# GSM_UnUsed.net
KiCad netlist of a schematic drawn in Altium Designer
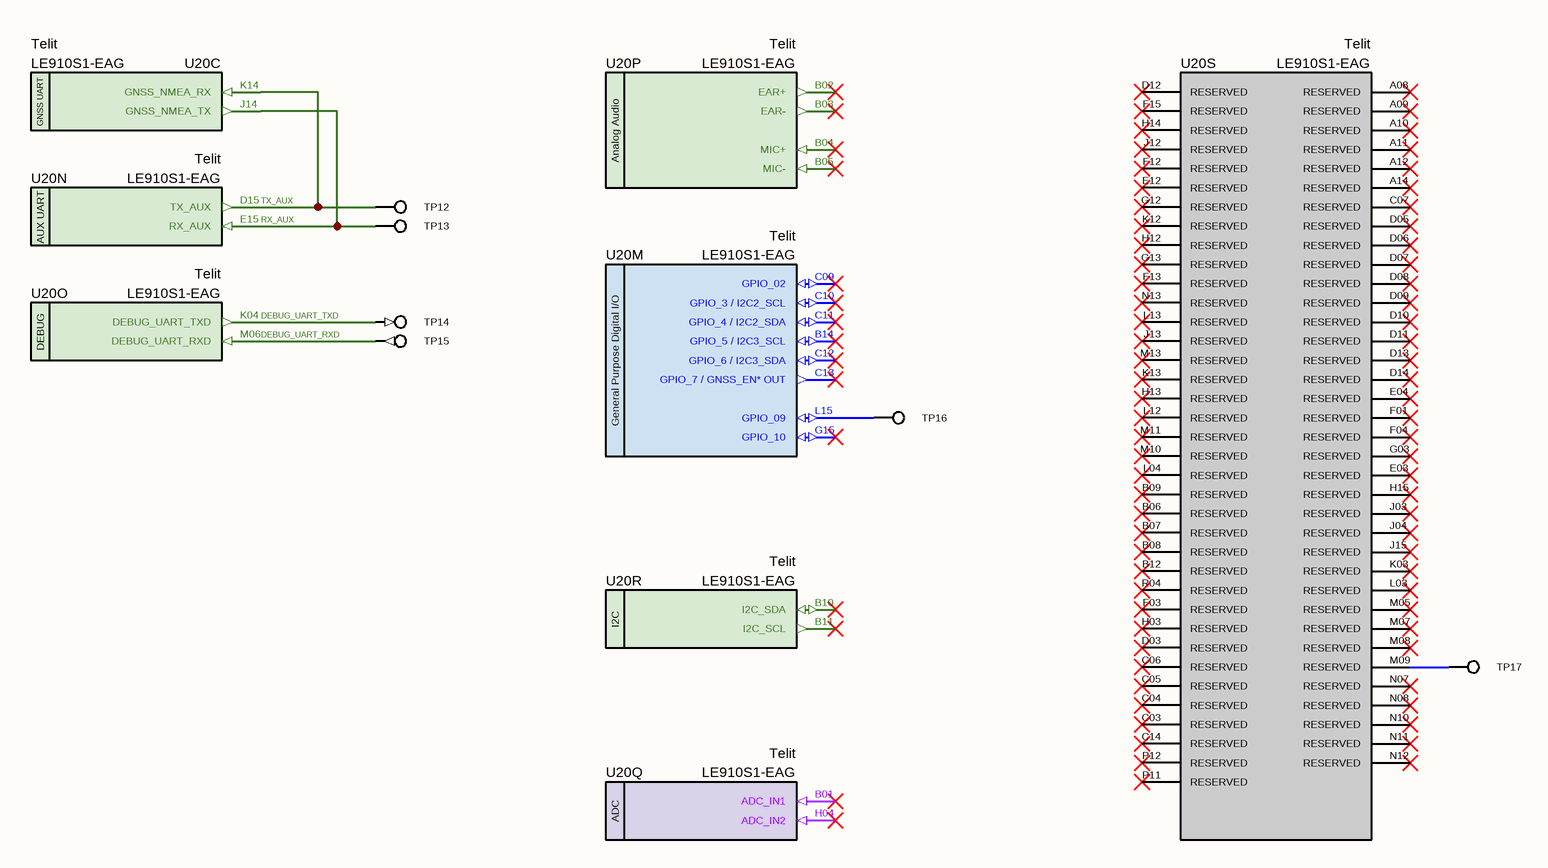
[diagram p0: GSM UnUsed.SchDoc]

(export (version "E")
  (design (tool "Eeschema 10.0.6"))
  (components
    (comp (ref "TP12")
      (value "TP - GSM_Power_EN")
      (footprint "TP")
      (description "Test Point")
      (libsource (lib "Akkoyun") (part "PCB - Test Point"))
    )
    (comp (ref "TP13")
      (value "TP - GSM_Power_EN")
      (footprint "TP")
      (description "Test Point")
      (libsource (lib "Akkoyun") (part "PCB - Test Point"))
    )
    (comp (ref "TP14")
      (value "TP - GSM_Power_EN")
      (footprint "TP")
      (description "Test Point")
      (libsource (lib "Akkoyun") (part "PCB - Test Point"))
    )
    (comp (ref "TP15")
      (value "TP - GSM_Power_EN")
      (footprint "TP")
      (description "Test Point")
      (libsource (lib "Akkoyun") (part "PCB - Test Point"))
    )
    (comp (ref "TP16")
      (value "TP - GSM_Power_EN")
      (footprint "TP")
      (description "Test Point")
      (libsource (lib "Akkoyun") (part "PCB - Test Point"))
    )
    (comp (ref "TP17")
      (value "TP - GSM_Power_EN")
      (footprint "TP")
      (description "Test Point")
      (libsource (lib "Akkoyun") (part "PCB - Test Point"))
    )
    (comp (ref "U20")
      (value "LE910S1-EAG LTE GSM Module")
      (footprint "LE910 GSM Modem")
      (description "Telit LE910S1-EAG GPRS/GNSS Module")
      (fields
        (field (name "MANUFACTURER PART NUMBER") "LE910S1-EAG")
        (field (name "MANUFACTURER NAME") "Telit")
      )
      (libsource (lib "") (part "IC - LE910S1-EAG_1"))
    )
  )
  (nets
    (net (code "1") (name "/DEBUG_UART_RXD") (class "Default")
      (node (ref "TP15") (pin "1") (pinfunction "1_1") (pintype "input"))
      (node (ref "U20") (pin "M06") (pinfunction "DEBUG_UART_RXD_M06") (pintype "input"))
    )
    (net (code "2") (name "/DEBUG_UART_TXD") (class "Default")
      (node (ref "TP14") (pin "1") (pinfunction "1_1") (pintype "input"))
      (node (ref "U20") (pin "K04") (pinfunction "DEBUG_UART_TXD_K04") (pintype "output"))
    )
    (net (code "3") (name "/RX_AUX") (class "Default")
      (node (ref "TP13") (pin "1") (pinfunction "1_1") (pintype "input"))
      (node (ref "U20") (pin "E15") (pinfunction "RX_AUX_E15") (pintype "input"))
      (node (ref "U20") (pin "J14") (pinfunction "GNSS_NMEA_TX_J14") (pintype "output"))
    )
    (net (code "4") (name "/TX_AUX") (class "Default")
      (node (ref "TP12") (pin "1") (pinfunction "1_1") (pintype "input"))
      (node (ref "U20") (pin "D15") (pinfunction "TX_AUX_D15") (pintype "output"))
      (node (ref "U20") (pin "K14") (pinfunction "GNSS_NMEA_RX_K14") (pintype "input"))
    )
    (net (code "5") (name "Net-(TP17-Pad1)") (class "Default")
      (node (ref "TP17") (pin "1") (pinfunction "1_1") (pintype "input"))
      (node (ref "U20") (pin "M09") (pinfunction "RESERVED_M09") (pintype "passive"))
    )
    (net (code "6") (name "Net-(U20M-GPIO_09)") (class "Default")
      (node (ref "TP16") (pin "1") (pinfunction "1_1") (pintype "input"))
      (node (ref "U20") (pin "L15") (pinfunction "GPIO_09_L15") (pintype "bidirectional"))
    )
    (net (code "7") (name "unconnected-(U20M-GPIO_02-PadC09)") (class "Default")
      (node (ref "U20") (pin "C09") (pinfunction "GPIO_02_C09") (pintype "bidirectional+no_connect"))
    )
    (net (code "8") (name "unconnected-(U20M-GPIO_3_{slash}_I2C2_SCL-PadC10)") (class "Default")
      (node (ref "U20") (pin "C10") (pinfunction "GPIO_3_/_I2C2_SCL_C10") (pintype "bidirectional+no_connect"))
    )
    (net (code "9") (name "unconnected-(U20M-GPIO_4_{slash}_I2C2_SDA-PadC11)") (class "Default")
      (node (ref "U20") (pin "C11") (pinfunction "GPIO_4_/_I2C2_SDA_C11") (pintype "bidirectional+no_connect"))
    )
    (net (code "10") (name "unconnected-(U20M-GPIO_5_{slash}_I2C3_SCL-PadB14)") (class "Default")
      (node (ref "U20") (pin "B14") (pinfunction "GPIO_5_/_I2C3_SCL_B14") (pintype "bidirectional+no_connect"))
    )
    (net (code "11") (name "unconnected-(U20M-GPIO_6_{slash}_I2C3_SDA-PadC12)") (class "Default")
      (node (ref "U20") (pin "C12") (pinfunction "GPIO_6_/_I2C3_SDA_C12") (pintype "bidirectional+no_connect"))
    )
    (net (code "12") (name "unconnected-(U20M-GPIO_7_{slash}_GNSS_EN*_OUT-PadC13)") (class "Default")
      (node (ref "U20") (pin "C13") (pinfunction "GPIO_7_/_GNSS_EN*_OUT_C13") (pintype "output+no_connect"))
    )
    (net (code "13") (name "unconnected-(U20M-GPIO_10-PadG15)") (class "Default")
      (node (ref "U20") (pin "G15") (pinfunction "GPIO_10_G15") (pintype "bidirectional+no_connect"))
    )
    (net (code "14") (name "unconnected-(U20P-EAR+-PadB02)") (class "Default")
      (node (ref "U20") (pin "B02") (pinfunction "EAR+_B02") (pintype "output+no_connect"))
    )
    (net (code "15") (name "unconnected-(U20P-EAR--PadB03)") (class "Default")
      (node (ref "U20") (pin "B03") (pinfunction "EAR-_B03") (pintype "output+no_connect"))
    )
    (net (code "16") (name "unconnected-(U20P-MIC+-PadB04)") (class "Default")
      (node (ref "U20") (pin "B04") (pinfunction "MIC+_B04") (pintype "input+no_connect"))
    )
    (net (code "17") (name "unconnected-(U20P-MIC--PadB05)") (class "Default")
      (node (ref "U20") (pin "B05") (pinfunction "MIC-_B05") (pintype "input+no_connect"))
    )
    (net (code "18") (name "unconnected-(U20Q-ADC_IN1-PadB01)") (class "Default")
      (node (ref "U20") (pin "B01") (pinfunction "ADC_IN1_B01") (pintype "input+no_connect"))
    )
    (net (code "19") (name "unconnected-(U20Q-ADC_IN2-PadH04)") (class "Default")
      (node (ref "U20") (pin "H04") (pinfunction "ADC_IN2_H04") (pintype "input+no_connect"))
    )
    (net (code "20") (name "unconnected-(U20R-I2C_SCL-PadB11)") (class "Default")
      (node (ref "U20") (pin "B11") (pinfunction "I2C_SCL_B11") (pintype "output+no_connect"))
    )
    (net (code "21") (name "unconnected-(U20R-I2C_SDA-PadB10)") (class "Default")
      (node (ref "U20") (pin "B10") (pinfunction "I2C_SDA_B10") (pintype "bidirectional+no_connect"))
    )
    (net (code "22") (name "unconnected-(U20S-RESERVED-PadA08)") (class "Default")
      (node (ref "U20") (pin "A08") (pinfunction "RESERVED_A08") (pintype "passive+no_connect"))
    )
    (net (code "23") (name "unconnected-(U20S-RESERVED-PadA09)") (class "Default")
      (node (ref "U20") (pin "A09") (pinfunction "RESERVED_A09") (pintype "passive+no_connect"))
    )
    (net (code "24") (name "unconnected-(U20S-RESERVED-PadA10)") (class "Default")
      (node (ref "U20") (pin "A10") (pinfunction "RESERVED_A10") (pintype "passive+no_connect"))
    )
    (net (code "25") (name "unconnected-(U20S-RESERVED-PadA11)") (class "Default")
      (node (ref "U20") (pin "A11") (pinfunction "RESERVED_A11") (pintype "passive+no_connect"))
    )
    (net (code "26") (name "unconnected-(U20S-RESERVED-PadA12)") (class "Default")
      (node (ref "U20") (pin "A12") (pinfunction "RESERVED_A12") (pintype "passive+no_connect"))
    )
    (net (code "27") (name "unconnected-(U20S-RESERVED-PadA14)") (class "Default")
      (node (ref "U20") (pin "A14") (pinfunction "RESERVED_A14") (pintype "passive+no_connect"))
    )
    (net (code "28") (name "unconnected-(U20S-RESERVED-PadB06)") (class "Default")
      (node (ref "U20") (pin "B06") (pinfunction "RESERVED_B06") (pintype "passive+no_connect"))
    )
    (net (code "29") (name "unconnected-(U20S-RESERVED-PadB07)") (class "Default")
      (node (ref "U20") (pin "B07") (pinfunction "RESERVED_B07") (pintype "passive+no_connect"))
    )
    (net (code "30") (name "unconnected-(U20S-RESERVED-PadB08)") (class "Default")
      (node (ref "U20") (pin "B08") (pinfunction "RESERVED_B08") (pintype "passive+no_connect"))
    )
    (net (code "31") (name "unconnected-(U20S-RESERVED-PadB09)") (class "Default")
      (node (ref "U20") (pin "B09") (pinfunction "RESERVED_B09") (pintype "passive+no_connect"))
    )
    (net (code "32") (name "unconnected-(U20S-RESERVED-PadB12)") (class "Default")
      (node (ref "U20") (pin "B12") (pinfunction "RESERVED_B12") (pintype "passive+no_connect"))
    )
    (net (code "33") (name "unconnected-(U20S-RESERVED-PadC03)") (class "Default")
      (node (ref "U20") (pin "C03") (pinfunction "RESERVED_C03") (pintype "passive+no_connect"))
    )
    (net (code "34") (name "unconnected-(U20S-RESERVED-PadC04)") (class "Default")
      (node (ref "U20") (pin "C04") (pinfunction "RESERVED_C04") (pintype "passive+no_connect"))
    )
    (net (code "35") (name "unconnected-(U20S-RESERVED-PadC05)") (class "Default")
      (node (ref "U20") (pin "C05") (pinfunction "RESERVED_C05") (pintype "passive+no_connect"))
    )
    (net (code "36") (name "unconnected-(U20S-RESERVED-PadC06)") (class "Default")
      (node (ref "U20") (pin "C06") (pinfunction "RESERVED_C06") (pintype "passive+no_connect"))
    )
    (net (code "37") (name "unconnected-(U20S-RESERVED-PadC07)") (class "Default")
      (node (ref "U20") (pin "C07") (pinfunction "RESERVED_C07") (pintype "passive+no_connect"))
    )
    (net (code "38") (name "unconnected-(U20S-RESERVED-PadC14)") (class "Default")
      (node (ref "U20") (pin "C14") (pinfunction "RESERVED_C14") (pintype "passive+no_connect"))
    )
    (net (code "39") (name "unconnected-(U20S-RESERVED-PadD03)") (class "Default")
      (node (ref "U20") (pin "D03") (pinfunction "RESERVED_D03") (pintype "passive+no_connect"))
    )
    (net (code "40") (name "unconnected-(U20S-RESERVED-PadD05)") (class "Default")
      (node (ref "U20") (pin "D05") (pinfunction "RESERVED_D05") (pintype "passive+no_connect"))
    )
    (net (code "41") (name "unconnected-(U20S-RESERVED-PadD06)") (class "Default")
      (node (ref "U20") (pin "D06") (pinfunction "RESERVED_D06") (pintype "passive+no_connect"))
    )
    (net (code "42") (name "unconnected-(U20S-RESERVED-PadD07)") (class "Default")
      (node (ref "U20") (pin "D07") (pinfunction "RESERVED_D07") (pintype "passive+no_connect"))
    )
    (net (code "43") (name "unconnected-(U20S-RESERVED-PadD08)") (class "Default")
      (node (ref "U20") (pin "D08") (pinfunction "RESERVED_D08") (pintype "passive+no_connect"))
    )
    (net (code "44") (name "unconnected-(U20S-RESERVED-PadD09)") (class "Default")
      (node (ref "U20") (pin "D09") (pinfunction "RESERVED_D09") (pintype "passive+no_connect"))
    )
    (net (code "45") (name "unconnected-(U20S-RESERVED-PadD10)") (class "Default")
      (node (ref "U20") (pin "D10") (pinfunction "RESERVED_D10") (pintype "passive+no_connect"))
    )
    (net (code "46") (name "unconnected-(U20S-RESERVED-PadD11)") (class "Default")
      (node (ref "U20") (pin "D11") (pinfunction "RESERVED_D11") (pintype "passive+no_connect"))
    )
    (net (code "47") (name "unconnected-(U20S-RESERVED-PadD12)") (class "Default")
      (node (ref "U20") (pin "D12") (pinfunction "RESERVED_D12") (pintype "passive+no_connect"))
    )
    (net (code "48") (name "unconnected-(U20S-RESERVED-PadD13)") (class "Default")
      (node (ref "U20") (pin "D13") (pinfunction "RESERVED_D13") (pintype "passive+no_connect"))
    )
    (net (code "49") (name "unconnected-(U20S-RESERVED-PadD14)") (class "Default")
      (node (ref "U20") (pin "D14") (pinfunction "RESERVED_D14") (pintype "passive+no_connect"))
    )
    (net (code "50") (name "unconnected-(U20S-RESERVED-PadE03)") (class "Default")
      (node (ref "U20") (pin "E03") (pinfunction "RESERVED_E03") (pintype "passive+no_connect"))
    )
    (net (code "51") (name "unconnected-(U20S-RESERVED-PadE04)") (class "Default")
      (node (ref "U20") (pin "E04") (pinfunction "RESERVED_E04") (pintype "passive+no_connect"))
    )
    (net (code "52") (name "unconnected-(U20S-RESERVED-PadE12)") (class "Default")
      (node (ref "U20") (pin "E12") (pinfunction "RESERVED_E12") (pintype "passive+no_connect"))
    )
    (net (code "53") (name "unconnected-(U20S-RESERVED-PadF01)") (class "Default")
      (node (ref "U20") (pin "F01") (pinfunction "RESERVED_F01") (pintype "passive+no_connect"))
    )
    (net (code "54") (name "unconnected-(U20S-RESERVED-PadF03)") (class "Default")
      (node (ref "U20") (pin "F03") (pinfunction "RESERVED_F03") (pintype "passive+no_connect"))
    )
    (net (code "55") (name "unconnected-(U20S-RESERVED-PadF04)") (class "Default")
      (node (ref "U20") (pin "F04") (pinfunction "RESERVED_F04") (pintype "passive+no_connect"))
    )
    (net (code "56") (name "unconnected-(U20S-RESERVED-PadF12)") (class "Default")
      (node (ref "U20") (pin "F12") (pinfunction "RESERVED_F12") (pintype "passive+no_connect"))
    )
    (net (code "57") (name "unconnected-(U20S-RESERVED-PadF13)") (class "Default")
      (node (ref "U20") (pin "F13") (pinfunction "RESERVED_F13") (pintype "passive+no_connect"))
    )
    (net (code "58") (name "unconnected-(U20S-RESERVED-PadF15)") (class "Default")
      (node (ref "U20") (pin "F15") (pinfunction "RESERVED_F15") (pintype "passive+no_connect"))
    )
    (net (code "59") (name "unconnected-(U20S-RESERVED-PadG03)") (class "Default")
      (node (ref "U20") (pin "G03") (pinfunction "RESERVED_G03") (pintype "passive+no_connect"))
    )
    (net (code "60") (name "unconnected-(U20S-RESERVED-PadG12)") (class "Default")
      (node (ref "U20") (pin "G12") (pinfunction "RESERVED_G12") (pintype "passive+no_connect"))
    )
    (net (code "61") (name "unconnected-(U20S-RESERVED-PadG13)") (class "Default")
      (node (ref "U20") (pin "G13") (pinfunction "RESERVED_G13") (pintype "passive+no_connect"))
    )
    (net (code "62") (name "unconnected-(U20S-RESERVED-PadH03)") (class "Default")
      (node (ref "U20") (pin "H03") (pinfunction "RESERVED_H03") (pintype "passive+no_connect"))
    )
    (net (code "63") (name "unconnected-(U20S-RESERVED-PadH12)") (class "Default")
      (node (ref "U20") (pin "H12") (pinfunction "RESERVED_H12") (pintype "passive+no_connect"))
    )
    (net (code "64") (name "unconnected-(U20S-RESERVED-PadH13)") (class "Default")
      (node (ref "U20") (pin "H13") (pinfunction "RESERVED_H13") (pintype "passive+no_connect"))
    )
    (net (code "65") (name "unconnected-(U20S-RESERVED-PadH14)") (class "Default")
      (node (ref "U20") (pin "H14") (pinfunction "RESERVED_H14") (pintype "passive+no_connect"))
    )
    (net (code "66") (name "unconnected-(U20S-RESERVED-PadH15)") (class "Default")
      (node (ref "U20") (pin "H15") (pinfunction "RESERVED_H15") (pintype "passive+no_connect"))
    )
    (net (code "67") (name "unconnected-(U20S-RESERVED-PadJ03)") (class "Default")
      (node (ref "U20") (pin "J03") (pinfunction "RESERVED_J03") (pintype "passive+no_connect"))
    )
    (net (code "68") (name "unconnected-(U20S-RESERVED-PadJ04)") (class "Default")
      (node (ref "U20") (pin "J04") (pinfunction "RESERVED_J04") (pintype "passive+no_connect"))
    )
    (net (code "69") (name "unconnected-(U20S-RESERVED-PadJ12)") (class "Default")
      (node (ref "U20") (pin "J12") (pinfunction "RESERVED_J12") (pintype "passive+no_connect"))
    )
    (net (code "70") (name "unconnected-(U20S-RESERVED-PadJ13)") (class "Default")
      (node (ref "U20") (pin "J13") (pinfunction "RESERVED_J13") (pintype "passive+no_connect"))
    )
    (net (code "71") (name "unconnected-(U20S-RESERVED-PadJ15)") (class "Default")
      (node (ref "U20") (pin "J15") (pinfunction "RESERVED_J15") (pintype "passive+no_connect"))
    )
    (net (code "72") (name "unconnected-(U20S-RESERVED-PadK03)") (class "Default")
      (node (ref "U20") (pin "K03") (pinfunction "RESERVED_K03") (pintype "passive+no_connect"))
    )
    (net (code "73") (name "unconnected-(U20S-RESERVED-PadK12)") (class "Default")
      (node (ref "U20") (pin "K12") (pinfunction "RESERVED_K12") (pintype "passive+no_connect"))
    )
    (net (code "74") (name "unconnected-(U20S-RESERVED-PadK13)") (class "Default")
      (node (ref "U20") (pin "K13") (pinfunction "RESERVED_K13") (pintype "passive+no_connect"))
    )
    (net (code "75") (name "unconnected-(U20S-RESERVED-PadL03)") (class "Default")
      (node (ref "U20") (pin "L03") (pinfunction "RESERVED_L03") (pintype "passive+no_connect"))
    )
    (net (code "76") (name "unconnected-(U20S-RESERVED-PadL04)") (class "Default")
      (node (ref "U20") (pin "L04") (pinfunction "RESERVED_L04") (pintype "passive+no_connect"))
    )
    (net (code "77") (name "unconnected-(U20S-RESERVED-PadL12)") (class "Default")
      (node (ref "U20") (pin "L12") (pinfunction "RESERVED_L12") (pintype "passive+no_connect"))
    )
    (net (code "78") (name "unconnected-(U20S-RESERVED-PadL13)") (class "Default")
      (node (ref "U20") (pin "L13") (pinfunction "RESERVED_L13") (pintype "passive+no_connect"))
    )
    (net (code "79") (name "unconnected-(U20S-RESERVED-PadM05)") (class "Default")
      (node (ref "U20") (pin "M05") (pinfunction "RESERVED_M05") (pintype "passive+no_connect"))
    )
    (net (code "80") (name "unconnected-(U20S-RESERVED-PadM07)") (class "Default")
      (node (ref "U20") (pin "M07") (pinfunction "RESERVED_M07") (pintype "passive+no_connect"))
    )
    (net (code "81") (name "unconnected-(U20S-RESERVED-PadM08)") (class "Default")
      (node (ref "U20") (pin "M08") (pinfunction "RESERVED_M08") (pintype "passive+no_connect"))
    )
    (net (code "82") (name "unconnected-(U20S-RESERVED-PadM10)") (class "Default")
      (node (ref "U20") (pin "M10") (pinfunction "RESERVED_M10") (pintype "passive+no_connect"))
    )
    (net (code "83") (name "unconnected-(U20S-RESERVED-PadM11)") (class "Default")
      (node (ref "U20") (pin "M11") (pinfunction "RESERVED_M11") (pintype "passive+no_connect"))
    )
    (net (code "84") (name "unconnected-(U20S-RESERVED-PadM13)") (class "Default")
      (node (ref "U20") (pin "M13") (pinfunction "RESERVED_M13") (pintype "passive+no_connect"))
    )
    (net (code "85") (name "unconnected-(U20S-RESERVED-PadN07)") (class "Default")
      (node (ref "U20") (pin "N07") (pinfunction "RESERVED_N07") (pintype "passive+no_connect"))
    )
    (net (code "86") (name "unconnected-(U20S-RESERVED-PadN08)") (class "Default")
      (node (ref "U20") (pin "N08") (pinfunction "RESERVED_N08") (pintype "passive+no_connect"))
    )
    (net (code "87") (name "unconnected-(U20S-RESERVED-PadN10)") (class "Default")
      (node (ref "U20") (pin "N10") (pinfunction "RESERVED_N10") (pintype "passive+no_connect"))
    )
    (net (code "88") (name "unconnected-(U20S-RESERVED-PadN11)") (class "Default")
      (node (ref "U20") (pin "N11") (pinfunction "RESERVED_N11") (pintype "passive+no_connect"))
    )
    (net (code "89") (name "unconnected-(U20S-RESERVED-PadN12)") (class "Default")
      (node (ref "U20") (pin "N12") (pinfunction "RESERVED_N12") (pintype "passive+no_connect"))
    )
    (net (code "90") (name "unconnected-(U20S-RESERVED-PadN13)") (class "Default")
      (node (ref "U20") (pin "N13") (pinfunction "RESERVED_N13") (pintype "passive+no_connect"))
    )
    (net (code "91") (name "unconnected-(U20S-RESERVED-PadP11)") (class "Default")
      (node (ref "U20") (pin "P11") (pinfunction "RESERVED_P11") (pintype "passive+no_connect"))
    )
    (net (code "92") (name "unconnected-(U20S-RESERVED-PadP12)") (class "Default")
      (node (ref "U20") (pin "P12") (pinfunction "RESERVED_P12") (pintype "passive+no_connect"))
    )
    (net (code "93") (name "unconnected-(U20S-RESERVED-PadR04)") (class "Default")
      (node (ref "U20") (pin "R04") (pinfunction "RESERVED_R04") (pintype "power_in+no_connect"))
    )
  )
)
